# Ring.net
KiCad netlist of a schematic drawn in Altium Designer
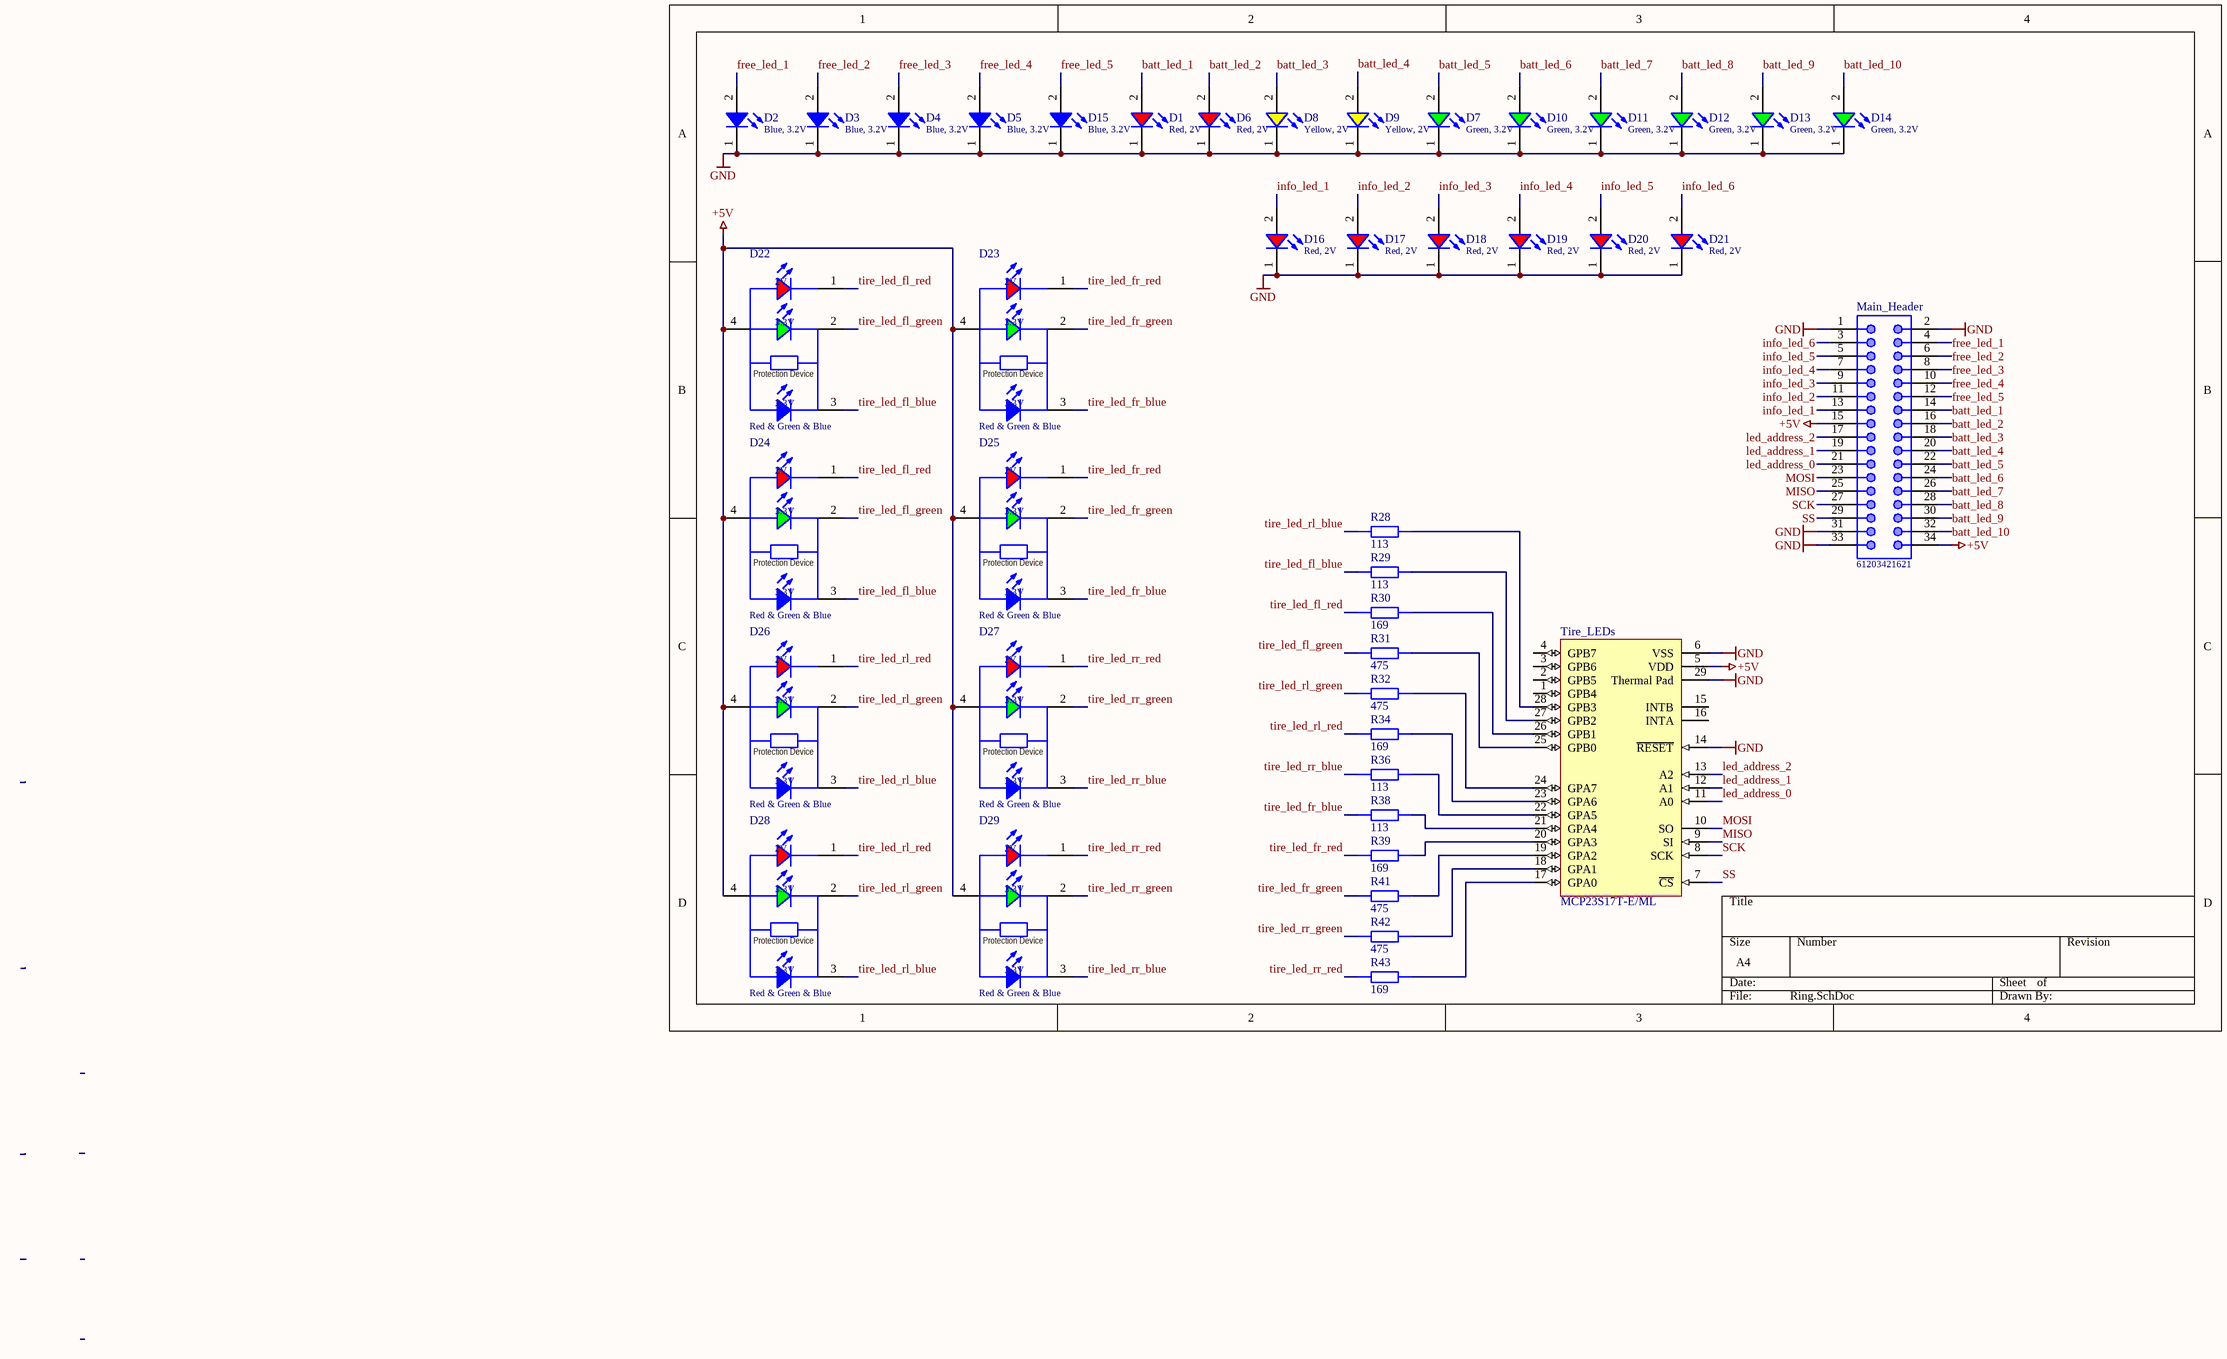
[diagram p0: Ring.SchDoc]

(export (version "E")
  (design (tool "Eeschema 10.0.6"))
  (components
    (comp (ref "D1")
      (value "Red, 2V")
      (footprint "WL-SMCW_0805")
      (description "WL-SMCW SMT Mono-color Chip LED Waterclear, size 0805, Red, 2V, 140deg")
      (fields (field (name "PART NUMBER") "150080RS75000") (field (name "PUBLISHER") "Wurth Elektronik"))
      (libsource (lib "Altium_WL-SMCW (rev20a)") (part "150080RS75000"))
    )
    (comp (ref "D2")
      (value "Blue, 3.2V")
      (footprint "WL-SMCW_0805")
      (description "WL-SMCW SMT Mono-color Chip LED Waterclear, size 0805, Blue, 3.2V, 140deg")
      (fields (field (name "PART NUMBER") "150080BS75000") (field (name "PUBLISHER") "Wurth Elektronik"))
      (libsource (lib "Altium_WL-SMCW (rev20a)") (part "150080BS75000"))
    )
    (comp (ref "D3")
      (value "Blue, 3.2V")
      (footprint "WL-SMCW_0805")
      (description "WL-SMCW SMT Mono-color Chip LED Waterclear, size 0805, Blue, 3.2V, 140deg")
      (fields (field (name "PART NUMBER") "150080BS75000") (field (name "PUBLISHER") "Wurth Elektronik"))
      (libsource (lib "Altium_WL-SMCW (rev20a)") (part "150080BS75000"))
    )
    (comp (ref "D4")
      (value "Blue, 3.2V")
      (footprint "WL-SMCW_0805")
      (description "WL-SMCW SMT Mono-color Chip LED Waterclear, size 0805, Blue, 3.2V, 140deg")
      (fields (field (name "PART NUMBER") "150080BS75000") (field (name "PUBLISHER") "Wurth Elektronik"))
      (libsource (lib "Altium_WL-SMCW (rev20a)") (part "150080BS75000"))
    )
    (comp (ref "D5")
      (value "Blue, 3.2V")
      (footprint "WL-SMCW_0805")
      (description "WL-SMCW SMT Mono-color Chip LED Waterclear, size 0805, Blue, 3.2V, 140deg")
      (fields (field (name "PART NUMBER") "150080BS75000") (field (name "PUBLISHER") "Wurth Elektronik"))
      (libsource (lib "Altium_WL-SMCW (rev20a)") (part "150080BS75000"))
    )
    (comp (ref "D6")
      (value "Red, 2V")
      (footprint "WL-SMCW_0805")
      (description "WL-SMCW SMT Mono-color Chip LED Waterclear, size 0805, Red, 2V, 140deg")
      (fields (field (name "PART NUMBER") "150080RS75000") (field (name "PUBLISHER") "Wurth Elektronik"))
      (libsource (lib "Altium_WL-SMCW (rev20a)") (part "150080RS75000"))
    )
    (comp (ref "D7")
      (value "Green, 3.2V")
      (footprint "WL-SMCW_0805")
      (description "WL-SMCW SMT Mono-color Chip LED Waterclear, size 0805, Green, 3.2V, 140deg")
      (fields (field (name "PART NUMBER") "150080GS75000") (field (name "PUBLISHER") "Wurth Elektronik"))
      (libsource (lib "Altium_WL-SMCW (rev20a)") (part "150080GS75000"))
    )
    (comp (ref "D8")
      (value "Yellow, 2V")
      (footprint "WL-SMCW_0805")
      (description "WL-SMCW SMT Mono-color Chip LED Waterclear, size 0805, Yellow, 2V, 140deg")
      (fields (field (name "PART NUMBER") "150080YS75000") (field (name "PUBLISHER") "Wurth Elektronik"))
      (libsource (lib "Altium_WL-SMCW (rev20a)") (part "150080YS75000"))
    )
    (comp (ref "D9")
      (value "Yellow, 2V")
      (footprint "WL-SMCW_0805")
      (description "WL-SMCW SMT Mono-color Chip LED Waterclear, size 0805, Yellow, 2V, 140deg")
      (fields (field (name "PART NUMBER") "150080YS75000") (field (name "PUBLISHER") "Wurth Elektronik"))
      (libsource (lib "Altium_WL-SMCW (rev20a)") (part "150080YS75000"))
    )
    (comp (ref "D10")
      (value "Green, 3.2V")
      (footprint "WL-SMCW_0805")
      (description "WL-SMCW SMT Mono-color Chip LED Waterclear, size 0805, Green, 3.2V, 140deg")
      (fields (field (name "PART NUMBER") "150080GS75000") (field (name "PUBLISHER") "Wurth Elektronik"))
      (libsource (lib "Altium_WL-SMCW (rev20a)") (part "150080GS75000"))
    )
    (comp (ref "D11")
      (value "Green, 3.2V")
      (footprint "WL-SMCW_0805")
      (description "WL-SMCW SMT Mono-color Chip LED Waterclear, size 0805, Green, 3.2V, 140deg")
      (fields (field (name "PART NUMBER") "150080GS75000") (field (name "PUBLISHER") "Wurth Elektronik"))
      (libsource (lib "Altium_WL-SMCW (rev20a)") (part "150080GS75000"))
    )
    (comp (ref "D12")
      (value "Green, 3.2V")
      (footprint "WL-SMCW_0805")
      (description "WL-SMCW SMT Mono-color Chip LED Waterclear, size 0805, Green, 3.2V, 140deg")
      (fields (field (name "PART NUMBER") "150080GS75000") (field (name "PUBLISHER") "Wurth Elektronik"))
      (libsource (lib "Altium_WL-SMCW (rev20a)") (part "150080GS75000"))
    )
    (comp (ref "D13")
      (value "Green, 3.2V")
      (footprint "WL-SMCW_0805")
      (description "WL-SMCW SMT Mono-color Chip LED Waterclear, size 0805, Green, 3.2V, 140deg")
      (fields (field (name "PART NUMBER") "150080GS75000") (field (name "PUBLISHER") "Wurth Elektronik"))
      (libsource (lib "Altium_WL-SMCW (rev20a)") (part "150080GS75000"))
    )
    (comp (ref "D14")
      (value "Green, 3.2V")
      (footprint "WL-SMCW_0805")
      (description "WL-SMCW SMT Mono-color Chip LED Waterclear, size 0805, Green, 3.2V, 140deg")
      (fields (field (name "PART NUMBER") "150080GS75000") (field (name "PUBLISHER") "Wurth Elektronik"))
      (libsource (lib "Altium_WL-SMCW (rev20a)") (part "150080GS75000"))
    )
    (comp (ref "D15")
      (value "Blue, 3.2V")
      (footprint "WL-SMCW_0805")
      (description "WL-SMCW SMT Mono-color Chip LED Waterclear, size 0805, Blue, 3.2V, 140deg")
      (fields (field (name "PART NUMBER") "150080BS75000") (field (name "PUBLISHER") "Wurth Elektronik"))
      (libsource (lib "Altium_WL-SMCW (rev20a)") (part "150080BS75000"))
    )
    (comp (ref "D16")
      (value "Red, 2V")
      (footprint "WL-SMCW_0805")
      (description "WL-SMCW SMT Mono-color Chip LED Waterclear, size 0805, Red, 2V, 140deg")
      (fields (field (name "PART NUMBER") "150080RS75000") (field (name "PUBLISHER") "Wurth Elektronik"))
      (libsource (lib "Altium_WL-SMCW (rev20a)") (part "150080RS75000"))
    )
    (comp (ref "D17")
      (value "Red, 2V")
      (footprint "WL-SMCW_0805")
      (description "WL-SMCW SMT Mono-color Chip LED Waterclear, size 0805, Red, 2V, 140deg")
      (fields (field (name "PART NUMBER") "150080RS75000") (field (name "PUBLISHER") "Wurth Elektronik"))
      (libsource (lib "Altium_WL-SMCW (rev20a)") (part "150080RS75000"))
    )
    (comp (ref "D18")
      (value "Red, 2V")
      (footprint "WL-SMCW_0805")
      (description "WL-SMCW SMT Mono-color Chip LED Waterclear, size 0805, Red, 2V, 140deg")
      (fields (field (name "PART NUMBER") "150080RS75000") (field (name "PUBLISHER") "Wurth Elektronik"))
      (libsource (lib "Altium_WL-SMCW (rev20a)") (part "150080RS75000"))
    )
    (comp (ref "D19")
      (value "Red, 2V")
      (footprint "WL-SMCW_0805")
      (description "WL-SMCW SMT Mono-color Chip LED Waterclear, size 0805, Red, 2V, 140deg")
      (fields (field (name "PART NUMBER") "150080RS75000") (field (name "PUBLISHER") "Wurth Elektronik"))
      (libsource (lib "Altium_WL-SMCW (rev20a)") (part "150080RS75000"))
    )
    (comp (ref "D20")
      (value "Red, 2V")
      (footprint "WL-SMCW_0805")
      (description "WL-SMCW SMT Mono-color Chip LED Waterclear, size 0805, Red, 2V, 140deg")
      (fields (field (name "PART NUMBER") "150080RS75000") (field (name "PUBLISHER") "Wurth Elektronik"))
      (libsource (lib "Altium_WL-SMCW (rev20a)") (part "150080RS75000"))
    )
    (comp (ref "D21")
      (value "Red, 2V")
      (footprint "WL-SMCW_0805")
      (description "WL-SMCW SMT Mono-color Chip LED Waterclear, size 0805, Red, 2V, 140deg")
      (fields (field (name "PART NUMBER") "150080RS75000") (field (name "PUBLISHER") "Wurth Elektronik"))
      (libsource (lib "Altium_WL-SMCW (rev20a)") (part "150080RS75000"))
    )
    (comp (ref "D22")
      (value "Red & Green & Blue")
      (footprint "WL-SFCW_0805")
      (description "WL-SFCW SMT Full-color Chip LED Waterclear, size 0805, Red & Green & Blue, 120deg")
      (fields (field (name "PART NUMBER") "150080M173000") (field (name "PUBLISHER") "Wurth Elektronik"))
      (libsource (lib "Altium_WL-SFCW (rev19b)") (part "150080M173000"))
    )
    (comp (ref "D23")
      (value "Red & Green & Blue")
      (footprint "WL-SFCW_0805")
      (description "WL-SFCW SMT Full-color Chip LED Waterclear, size 0805, Red & Green & Blue, 120deg")
      (fields (field (name "PART NUMBER") "150080M173000") (field (name "PUBLISHER") "Wurth Elektronik"))
      (libsource (lib "Altium_WL-SFCW (rev19b)") (part "150080M173000"))
    )
    (comp (ref "D24")
      (value "Red & Green & Blue")
      (footprint "WL-SFCW_0805")
      (description "WL-SFCW SMT Full-color Chip LED Waterclear, size 0805, Red & Green & Blue, 120deg")
      (fields (field (name "PART NUMBER") "150080M173000") (field (name "PUBLISHER") "Wurth Elektronik"))
      (libsource (lib "Altium_WL-SFCW (rev19b)") (part "150080M173000"))
    )
    (comp (ref "D25")
      (value "Red & Green & Blue")
      (footprint "WL-SFCW_0805")
      (description "WL-SFCW SMT Full-color Chip LED Waterclear, size 0805, Red & Green & Blue, 120deg")
      (fields (field (name "PART NUMBER") "150080M173000") (field (name "PUBLISHER") "Wurth Elektronik"))
      (libsource (lib "Altium_WL-SFCW (rev19b)") (part "150080M173000"))
    )
    (comp (ref "D26")
      (value "Red & Green & Blue")
      (footprint "WL-SFCW_0805")
      (description "WL-SFCW SMT Full-color Chip LED Waterclear, size 0805, Red & Green & Blue, 120deg")
      (fields (field (name "PART NUMBER") "150080M173000") (field (name "PUBLISHER") "Wurth Elektronik"))
      (libsource (lib "Altium_WL-SFCW (rev19b)") (part "150080M173000"))
    )
    (comp (ref "D27")
      (value "Red & Green & Blue")
      (footprint "WL-SFCW_0805")
      (description "WL-SFCW SMT Full-color Chip LED Waterclear, size 0805, Red & Green & Blue, 120deg")
      (fields (field (name "PART NUMBER") "150080M173000") (field (name "PUBLISHER") "Wurth Elektronik"))
      (libsource (lib "Altium_WL-SFCW (rev19b)") (part "150080M173000"))
    )
    (comp (ref "D28")
      (value "Red & Green & Blue")
      (footprint "WL-SFCW_0805")
      (description "WL-SFCW SMT Full-color Chip LED Waterclear, size 0805, Red & Green & Blue, 120deg")
      (fields (field (name "PART NUMBER") "150080M173000") (field (name "PUBLISHER") "Wurth Elektronik"))
      (libsource (lib "Altium_WL-SFCW (rev19b)") (part "150080M173000"))
    )
    (comp (ref "D29")
      (value "Red & Green & Blue")
      (footprint "WL-SFCW_0805")
      (description "WL-SFCW SMT Full-color Chip LED Waterclear, size 0805, Red & Green & Blue, 120deg")
      (fields (field (name "PART NUMBER") "150080M173000") (field (name "PUBLISHER") "Wurth Elektronik"))
      (libsource (lib "Altium_WL-SFCW (rev19b)") (part "150080M173000"))
    )
    (comp (ref "Main_Header")
      (value "61203421621")
      (footprint "61203421621")
      (description "WR-BHD Box Header, Male PCB side, pitch 2.54mm, THT, Straight, 34p")
      (fields (field (name "MANUFACTURER") "Wurth Elektronik"))
      (libsource (lib "Altium_WR-BHD (rev21a)") (part "61203421621"))
    )
    (comp (ref "R28")
      (value "113")
      (footprint "STACKPOLE CSR0603")
      (description "Resistor with multiple footprints")
      (fields (field (name "Comment") "SMD Resistor"))
      (libsource (lib "Standardbauteile") (part "SMD Resistor"))
    )
    (comp (ref "R29")
      (value "113")
      (footprint "STACKPOLE CSR0603")
      (description "Resistor with multiple footprints")
      (fields (field (name "Comment") "SMD Resistor"))
      (libsource (lib "Standardbauteile") (part "SMD Resistor"))
    )
    (comp (ref "R30")
      (value "169")
      (footprint "STACKPOLE CSR0603")
      (description "Resistor with multiple footprints")
      (fields (field (name "Comment") "SMD Resistor"))
      (libsource (lib "Standardbauteile") (part "SMD Resistor"))
    )
    (comp (ref "R31")
      (value "475")
      (footprint "STACKPOLE CSR0603")
      (description "Resistor with multiple footprints")
      (fields (field (name "Comment") "SMD Resistor"))
      (libsource (lib "Standardbauteile") (part "SMD Resistor"))
    )
    (comp (ref "R32")
      (value "475")
      (footprint "STACKPOLE CSR0603")
      (description "Resistor with multiple footprints")
      (fields (field (name "Comment") "SMD Resistor"))
      (libsource (lib "Standardbauteile") (part "SMD Resistor"))
    )
    (comp (ref "R34")
      (value "169")
      (footprint "STACKPOLE CSR0603")
      (description "Resistor with multiple footprints")
      (fields (field (name "Comment") "SMD Resistor"))
      (libsource (lib "Standardbauteile") (part "SMD Resistor"))
    )
    (comp (ref "R36")
      (value "113")
      (footprint "STACKPOLE CSR0603")
      (description "Resistor with multiple footprints")
      (fields (field (name "Comment") "SMD Resistor"))
      (libsource (lib "Standardbauteile") (part "SMD Resistor"))
    )
    (comp (ref "R38")
      (value "113")
      (footprint "STACKPOLE CSR0603")
      (description "Resistor with multiple footprints")
      (fields (field (name "Comment") "SMD Resistor"))
      (libsource (lib "Standardbauteile") (part "SMD Resistor"))
    )
    (comp (ref "R39")
      (value "169")
      (footprint "STACKPOLE CSR0603")
      (description "Resistor with multiple footprints")
      (fields (field (name "Comment") "SMD Resistor"))
      (libsource (lib "Standardbauteile") (part "SMD Resistor"))
    )
    (comp (ref "R41")
      (value "475")
      (footprint "STACKPOLE CSR0603")
      (description "Resistor with multiple footprints")
      (fields (field (name "Comment") "SMD Resistor"))
      (libsource (lib "Standardbauteile") (part "SMD Resistor"))
    )
    (comp (ref "R42")
      (value "475")
      (footprint "STACKPOLE CSR0603")
      (description "Resistor with multiple footprints")
      (fields (field (name "Comment") "SMD Resistor"))
      (libsource (lib "Standardbauteile") (part "SMD Resistor"))
    )
    (comp (ref "R43")
      (value "169")
      (footprint "STACKPOLE CSR0603")
      (description "Resistor with multiple footprints")
      (fields (field (name "Comment") "SMD Resistor"))
      (libsource (lib "Standardbauteile") (part "SMD Resistor"))
    )
    (comp (ref "Tire_LEDs")
      (value "MCP23S17T-E/ML")
      (footprint "QFN-ML28_M")
      (description "16-Bit I/O Expander with Serial Interface, 28-Pin QFN, Extended Temperature, Tape and Reel")
      (libsource (lib "Altium Content Vault") (part "PR-BUSIC-MCP23S17-29"))
    )
  )
  (nets
    (net (code "1") (name "+5V") (class "Default")
      (node (ref "D22") (pin "4") (pinfunction "A_4") (pintype "passive"))
      (node (ref "D23") (pin "4") (pinfunction "A_4") (pintype "passive"))
      (node (ref "D24") (pin "4") (pinfunction "A_4") (pintype "passive"))
      (node (ref "D25") (pin "4") (pinfunction "A_4") (pintype "passive"))
      (node (ref "D26") (pin "4") (pinfunction "A_4") (pintype "passive"))
      (node (ref "D27") (pin "4") (pinfunction "A_4") (pintype "passive"))
      (node (ref "D28") (pin "4") (pinfunction "A_4") (pintype "passive"))
      (node (ref "D29") (pin "4") (pinfunction "A_4") (pintype "passive"))
      (node (ref "Main_Header") (pin "15") (pinfunction "15_15") (pintype "passive"))
      (node (ref "Main_Header") (pin "34") (pinfunction "34_34") (pintype "passive"))
      (node (ref "Tire_LEDs") (pin "5") (pinfunction "VDD_5") (pintype "power_in"))
    )
    (net (code "2") (name "/MISO") (class "Default")
      (node (ref "Main_Header") (pin "25") (pinfunction "25_25") (pintype "passive"))
      (node (ref "Tire_LEDs") (pin "9") (pinfunction "SI_9") (pintype "input"))
    )
    (net (code "3") (name "/MOSI") (class "Default")
      (node (ref "Main_Header") (pin "23") (pinfunction "23_23") (pintype "passive"))
      (node (ref "Tire_LEDs") (pin "10") (pinfunction "SO_10") (pintype "tri_state"))
    )
    (net (code "4") (name "/SCK") (class "Default")
      (node (ref "Main_Header") (pin "27") (pinfunction "27_27") (pintype "passive"))
      (node (ref "Tire_LEDs") (pin "8") (pinfunction "SCK_8") (pintype "input"))
    )
    (net (code "5") (name "/SS") (class "Default")
      (node (ref "Main_Header") (pin "29") (pinfunction "29_29") (pintype "passive"))
      (node (ref "Tire_LEDs") (pin "7") (pinfunction "~{CS}_7") (pintype "input"))
    )
    (net (code "6") (name "/batt_led_1") (class "Default")
      (node (ref "D1") (pin "2") (pinfunction "A_2") (pintype "passive"))
      (node (ref "Main_Header") (pin "14") (pinfunction "14_14") (pintype "passive"))
    )
    (net (code "7") (name "/batt_led_2") (class "Default")
      (node (ref "D6") (pin "2") (pinfunction "A_2") (pintype "passive"))
      (node (ref "Main_Header") (pin "16") (pinfunction "16_16") (pintype "passive"))
    )
    (net (code "8") (name "/batt_led_3") (class "Default")
      (node (ref "D8") (pin "2") (pinfunction "A_2") (pintype "passive"))
      (node (ref "Main_Header") (pin "18") (pinfunction "18_18") (pintype "passive"))
    )
    (net (code "9") (name "/batt_led_4") (class "Default")
      (node (ref "D9") (pin "2") (pinfunction "A_2") (pintype "passive"))
      (node (ref "Main_Header") (pin "20") (pinfunction "20_20") (pintype "passive"))
    )
    (net (code "10") (name "/batt_led_5") (class "Default")
      (node (ref "D7") (pin "2") (pinfunction "A_2") (pintype "passive"))
      (node (ref "Main_Header") (pin "22") (pinfunction "22_22") (pintype "passive"))
    )
    (net (code "11") (name "/batt_led_6") (class "Default")
      (node (ref "D10") (pin "2") (pinfunction "A_2") (pintype "passive"))
      (node (ref "Main_Header") (pin "24") (pinfunction "24_24") (pintype "passive"))
    )
    (net (code "12") (name "/batt_led_7") (class "Default")
      (node (ref "D11") (pin "2") (pinfunction "A_2") (pintype "passive"))
      (node (ref "Main_Header") (pin "26") (pinfunction "26_26") (pintype "passive"))
    )
    (net (code "13") (name "/batt_led_8") (class "Default")
      (node (ref "D12") (pin "2") (pinfunction "A_2") (pintype "passive"))
      (node (ref "Main_Header") (pin "28") (pinfunction "28_28") (pintype "passive"))
    )
    (net (code "14") (name "/batt_led_9") (class "Default")
      (node (ref "D13") (pin "2") (pinfunction "A_2") (pintype "passive"))
      (node (ref "Main_Header") (pin "30") (pinfunction "30_30") (pintype "passive"))
    )
    (net (code "15") (name "/batt_led_10") (class "Default")
      (node (ref "D14") (pin "2") (pinfunction "A_2") (pintype "passive"))
      (node (ref "Main_Header") (pin "32") (pinfunction "32_32") (pintype "passive"))
    )
    (net (code "16") (name "/free_led_1") (class "Default")
      (node (ref "D2") (pin "2") (pinfunction "A_2") (pintype "passive"))
      (node (ref "Main_Header") (pin "4") (pinfunction "4_4") (pintype "passive"))
    )
    (net (code "17") (name "/free_led_2") (class "Default")
      (node (ref "D3") (pin "2") (pinfunction "A_2") (pintype "passive"))
      (node (ref "Main_Header") (pin "6") (pinfunction "6_6") (pintype "passive"))
    )
    (net (code "18") (name "/free_led_3") (class "Default")
      (node (ref "D4") (pin "2") (pinfunction "A_2") (pintype "passive"))
      (node (ref "Main_Header") (pin "8") (pinfunction "8_8") (pintype "passive"))
    )
    (net (code "19") (name "/free_led_4") (class "Default")
      (node (ref "D5") (pin "2") (pinfunction "A_2") (pintype "passive"))
      (node (ref "Main_Header") (pin "10") (pinfunction "10_10") (pintype "passive"))
    )
    (net (code "20") (name "/free_led_5") (class "Default")
      (node (ref "D15") (pin "2") (pinfunction "A_2") (pintype "passive"))
      (node (ref "Main_Header") (pin "12") (pinfunction "12_12") (pintype "passive"))
    )
    (net (code "21") (name "/info_led_1") (class "Default")
      (node (ref "D16") (pin "2") (pinfunction "A_2") (pintype "passive"))
      (node (ref "Main_Header") (pin "13") (pinfunction "13_13") (pintype "passive"))
    )
    (net (code "22") (name "/info_led_2") (class "Default")
      (node (ref "D17") (pin "2") (pinfunction "A_2") (pintype "passive"))
      (node (ref "Main_Header") (pin "11") (pinfunction "11_11") (pintype "passive"))
    )
    (net (code "23") (name "/info_led_3") (class "Default")
      (node (ref "D18") (pin "2") (pinfunction "A_2") (pintype "passive"))
      (node (ref "Main_Header") (pin "9") (pinfunction "9_9") (pintype "passive"))
    )
    (net (code "24") (name "/info_led_4") (class "Default")
      (node (ref "D19") (pin "2") (pinfunction "A_2") (pintype "passive"))
      (node (ref "Main_Header") (pin "7") (pinfunction "7_7") (pintype "passive"))
    )
    (net (code "25") (name "/info_led_5") (class "Default")
      (node (ref "D20") (pin "2") (pinfunction "A_2") (pintype "passive"))
      (node (ref "Main_Header") (pin "5") (pinfunction "5_5") (pintype "passive"))
    )
    (net (code "26") (name "/info_led_6") (class "Default")
      (node (ref "D21") (pin "2") (pinfunction "A_2") (pintype "passive"))
      (node (ref "Main_Header") (pin "3") (pinfunction "3_3") (pintype "passive"))
    )
    (net (code "27") (name "/led_address_0") (class "Default")
      (node (ref "Main_Header") (pin "21") (pinfunction "21_21") (pintype "passive"))
      (node (ref "Tire_LEDs") (pin "11") (pinfunction "A0_11") (pintype "input"))
    )
    (net (code "28") (name "/led_address_1") (class "Default")
      (node (ref "Main_Header") (pin "19") (pinfunction "19_19") (pintype "passive"))
      (node (ref "Tire_LEDs") (pin "12") (pinfunction "A1_12") (pintype "input"))
    )
    (net (code "29") (name "/led_address_2") (class "Default")
      (node (ref "Main_Header") (pin "17") (pinfunction "17_17") (pintype "passive"))
      (node (ref "Tire_LEDs") (pin "13") (pinfunction "A2_13") (pintype "input"))
    )
    (net (code "30") (name "/tire_led_fl_blue") (class "Default")
      (node (ref "D22") (pin "3") (pinfunction "K_3") (pintype "passive"))
      (node (ref "D24") (pin "3") (pinfunction "K_3") (pintype "passive"))
      (node (ref "R29") (pin "2") (pinfunction "2_2") (pintype "passive"))
    )
    (net (code "31") (name "/tire_led_fl_green") (class "Default")
      (node (ref "D22") (pin "2") (pinfunction "K_2") (pintype "passive"))
      (node (ref "D24") (pin "2") (pinfunction "K_2") (pintype "passive"))
      (node (ref "R31") (pin "2") (pinfunction "2_2") (pintype "passive"))
    )
    (net (code "32") (name "/tire_led_fl_red") (class "Default")
      (node (ref "D22") (pin "1") (pinfunction "K_1") (pintype "passive"))
      (node (ref "D24") (pin "1") (pinfunction "K_1") (pintype "passive"))
      (node (ref "R30") (pin "2") (pinfunction "2_2") (pintype "passive"))
    )
    (net (code "33") (name "/tire_led_fr_blue") (class "Default")
      (node (ref "D23") (pin "3") (pinfunction "K_3") (pintype "passive"))
      (node (ref "D25") (pin "3") (pinfunction "K_3") (pintype "passive"))
      (node (ref "R38") (pin "2") (pinfunction "2_2") (pintype "passive"))
    )
    (net (code "34") (name "/tire_led_fr_green") (class "Default")
      (node (ref "D23") (pin "2") (pinfunction "K_2") (pintype "passive"))
      (node (ref "D25") (pin "2") (pinfunction "K_2") (pintype "passive"))
      (node (ref "R41") (pin "2") (pinfunction "2_2") (pintype "passive"))
    )
    (net (code "35") (name "/tire_led_fr_red") (class "Default")
      (node (ref "D23") (pin "1") (pinfunction "K_1") (pintype "passive"))
      (node (ref "D25") (pin "1") (pinfunction "K_1") (pintype "passive"))
      (node (ref "R39") (pin "2") (pinfunction "2_2") (pintype "passive"))
    )
    (net (code "36") (name "/tire_led_rl_blue") (class "Default")
      (node (ref "D26") (pin "3") (pinfunction "K_3") (pintype "passive"))
      (node (ref "D28") (pin "3") (pinfunction "K_3") (pintype "passive"))
      (node (ref "R28") (pin "2") (pinfunction "2_2") (pintype "passive"))
    )
    (net (code "37") (name "/tire_led_rl_green") (class "Default")
      (node (ref "D26") (pin "2") (pinfunction "K_2") (pintype "passive"))
      (node (ref "D28") (pin "2") (pinfunction "K_2") (pintype "passive"))
      (node (ref "R32") (pin "2") (pinfunction "2_2") (pintype "passive"))
    )
    (net (code "38") (name "/tire_led_rl_red") (class "Default")
      (node (ref "D26") (pin "1") (pinfunction "K_1") (pintype "passive"))
      (node (ref "D28") (pin "1") (pinfunction "K_1") (pintype "passive"))
      (node (ref "R34") (pin "2") (pinfunction "2_2") (pintype "passive"))
    )
    (net (code "39") (name "/tire_led_rr_blue") (class "Default")
      (node (ref "D27") (pin "3") (pinfunction "K_3") (pintype "passive"))
      (node (ref "D29") (pin "3") (pinfunction "K_3") (pintype "passive"))
      (node (ref "R36") (pin "2") (pinfunction "2_2") (pintype "passive"))
    )
    (net (code "40") (name "/tire_led_rr_green") (class "Default")
      (node (ref "D27") (pin "2") (pinfunction "K_2") (pintype "passive"))
      (node (ref "D29") (pin "2") (pinfunction "K_2") (pintype "passive"))
      (node (ref "R42") (pin "2") (pinfunction "2_2") (pintype "passive"))
    )
    (net (code "41") (name "/tire_led_rr_red") (class "Default")
      (node (ref "D27") (pin "1") (pinfunction "K_1") (pintype "passive"))
      (node (ref "D29") (pin "1") (pinfunction "K_1") (pintype "passive"))
      (node (ref "R43") (pin "2") (pinfunction "2_2") (pintype "passive"))
    )
    (net (code "42") (name "GND") (class "Default")
      (node (ref "D1") (pin "1") (pinfunction "K_1") (pintype "passive"))
      (node (ref "D10") (pin "1") (pinfunction "K_1") (pintype "passive"))
      (node (ref "D11") (pin "1") (pinfunction "K_1") (pintype "passive"))
      (node (ref "D12") (pin "1") (pinfunction "K_1") (pintype "passive"))
      (node (ref "D13") (pin "1") (pinfunction "K_1") (pintype "passive"))
      (node (ref "D14") (pin "1") (pinfunction "K_1") (pintype "passive"))
      (node (ref "D15") (pin "1") (pinfunction "K_1") (pintype "passive"))
      (node (ref "D16") (pin "1") (pinfunction "K_1") (pintype "passive"))
      (node (ref "D17") (pin "1") (pinfunction "K_1") (pintype "passive"))
      (node (ref "D18") (pin "1") (pinfunction "K_1") (pintype "passive"))
      (node (ref "D19") (pin "1") (pinfunction "K_1") (pintype "passive"))
      (node (ref "D2") (pin "1") (pinfunction "K_1") (pintype "passive"))
      (node (ref "D20") (pin "1") (pinfunction "K_1") (pintype "passive"))
      (node (ref "D21") (pin "1") (pinfunction "K_1") (pintype "passive"))
      (node (ref "D3") (pin "1") (pinfunction "K_1") (pintype "passive"))
      (node (ref "D4") (pin "1") (pinfunction "K_1") (pintype "passive"))
      (node (ref "D5") (pin "1") (pinfunction "K_1") (pintype "passive"))
      (node (ref "D6") (pin "1") (pinfunction "K_1") (pintype "passive"))
      (node (ref "D7") (pin "1") (pinfunction "K_1") (pintype "passive"))
      (node (ref "D8") (pin "1") (pinfunction "K_1") (pintype "passive"))
      (node (ref "D9") (pin "1") (pinfunction "K_1") (pintype "passive"))
      (node (ref "Main_Header") (pin "1") (pinfunction "1_1") (pintype "passive"))
      (node (ref "Main_Header") (pin "2") (pinfunction "2_2") (pintype "passive"))
      (node (ref "Main_Header") (pin "31") (pinfunction "31_31") (pintype "passive"))
      (node (ref "Main_Header") (pin "33") (pinfunction "33_33") (pintype "passive"))
      (node (ref "Tire_LEDs") (pin "14") (pinfunction "~{RESET}_14") (pintype "input"))
      (node (ref "Tire_LEDs") (pin "29") (pinfunction "Thermal_Pad_29") (pintype "passive"))
      (node (ref "Tire_LEDs") (pin "6") (pinfunction "VSS_6") (pintype "power_in"))
    )
    (net (code "43") (name "Net-(Tire_LEDs-GPA0)") (class "Default")
      (node (ref "R43") (pin "1") (pinfunction "1_1") (pintype "passive"))
      (node (ref "Tire_LEDs") (pin "17") (pinfunction "GPA0_17") (pintype "bidirectional"))
    )
    (net (code "44") (name "Net-(Tire_LEDs-GPA1)") (class "Default")
      (node (ref "R42") (pin "1") (pinfunction "1_1") (pintype "passive"))
      (node (ref "Tire_LEDs") (pin "18") (pinfunction "GPA1_18") (pintype "bidirectional"))
    )
    (net (code "45") (name "Net-(Tire_LEDs-GPA2)") (class "Default")
      (node (ref "R41") (pin "1") (pinfunction "1_1") (pintype "passive"))
      (node (ref "Tire_LEDs") (pin "19") (pinfunction "GPA2_19") (pintype "bidirectional"))
    )
    (net (code "46") (name "Net-(Tire_LEDs-GPA3)") (class "Default")
      (node (ref "R39") (pin "1") (pinfunction "1_1") (pintype "passive"))
      (node (ref "Tire_LEDs") (pin "20") (pinfunction "GPA3_20") (pintype "bidirectional"))
    )
    (net (code "47") (name "Net-(Tire_LEDs-GPA4)") (class "Default")
      (node (ref "R38") (pin "1") (pinfunction "1_1") (pintype "passive"))
      (node (ref "Tire_LEDs") (pin "21") (pinfunction "GPA4_21") (pintype "bidirectional"))
    )
    (net (code "48") (name "Net-(Tire_LEDs-GPA5)") (class "Default")
      (node (ref "R36") (pin "1") (pinfunction "1_1") (pintype "passive"))
      (node (ref "Tire_LEDs") (pin "22") (pinfunction "GPA5_22") (pintype "bidirectional"))
    )
    (net (code "49") (name "Net-(Tire_LEDs-GPA6)") (class "Default")
      (node (ref "R34") (pin "1") (pinfunction "1_1") (pintype "passive"))
      (node (ref "Tire_LEDs") (pin "23") (pinfunction "GPA6_23") (pintype "bidirectional"))
    )
    (net (code "50") (name "Net-(Tire_LEDs-GPA7)") (class "Default")
      (node (ref "R32") (pin "1") (pinfunction "1_1") (pintype "passive"))
      (node (ref "Tire_LEDs") (pin "24") (pinfunction "GPA7_24") (pintype "bidirectional"))
    )
    (net (code "51") (name "Net-(Tire_LEDs-GPB0)") (class "Default")
      (node (ref "R31") (pin "1") (pinfunction "1_1") (pintype "passive"))
      (node (ref "Tire_LEDs") (pin "25") (pinfunction "GPB0_25") (pintype "bidirectional"))
    )
    (net (code "52") (name "Net-(Tire_LEDs-GPB1)") (class "Default")
      (node (ref "R30") (pin "1") (pinfunction "1_1") (pintype "passive"))
      (node (ref "Tire_LEDs") (pin "26") (pinfunction "GPB1_26") (pintype "bidirectional"))
    )
    (net (code "53") (name "Net-(Tire_LEDs-GPB2)") (class "Default")
      (node (ref "R29") (pin "1") (pinfunction "1_1") (pintype "passive"))
      (node (ref "Tire_LEDs") (pin "27") (pinfunction "GPB2_27") (pintype "bidirectional"))
    )
    (net (code "54") (name "Net-(Tire_LEDs-GPB3)") (class "Default")
      (node (ref "R28") (pin "1") (pinfunction "1_1") (pintype "passive"))
      (node (ref "Tire_LEDs") (pin "28") (pinfunction "GPB3_28") (pintype "bidirectional"))
    )
    (net (code "55") (name "unconnected-(Tire_LEDs-GPB4-Pad1)") (class "Default")
      (node (ref "Tire_LEDs") (pin "1") (pinfunction "GPB4_1") (pintype "bidirectional"))
    )
    (net (code "56") (name "unconnected-(Tire_LEDs-GPB5-Pad2)") (class "Default")
      (node (ref "Tire_LEDs") (pin "2") (pinfunction "GPB5_2") (pintype "bidirectional"))
    )
    (net (code "57") (name "unconnected-(Tire_LEDs-GPB6-Pad3)") (class "Default")
      (node (ref "Tire_LEDs") (pin "3") (pinfunction "GPB6_3") (pintype "bidirectional"))
    )
    (net (code "58") (name "unconnected-(Tire_LEDs-GPB7-Pad4)") (class "Default")
      (node (ref "Tire_LEDs") (pin "4") (pinfunction "GPB7_4") (pintype "bidirectional"))
    )
    (net (code "59") (name "unconnected-(Tire_LEDs-INTA-Pad16)") (class "Default")
      (node (ref "Tire_LEDs") (pin "16") (pinfunction "INTA_16") (pintype "open_collector"))
    )
    (net (code "60") (name "unconnected-(Tire_LEDs-INTB-Pad15)") (class "Default")
      (node (ref "Tire_LEDs") (pin "15") (pinfunction "INTB_15") (pintype "open_collector"))
    )
  )
)
